# Greinke_Boost_Converter_Motor_Schematic.net
KiCad netlist of a schematic drawn in Altium Designer
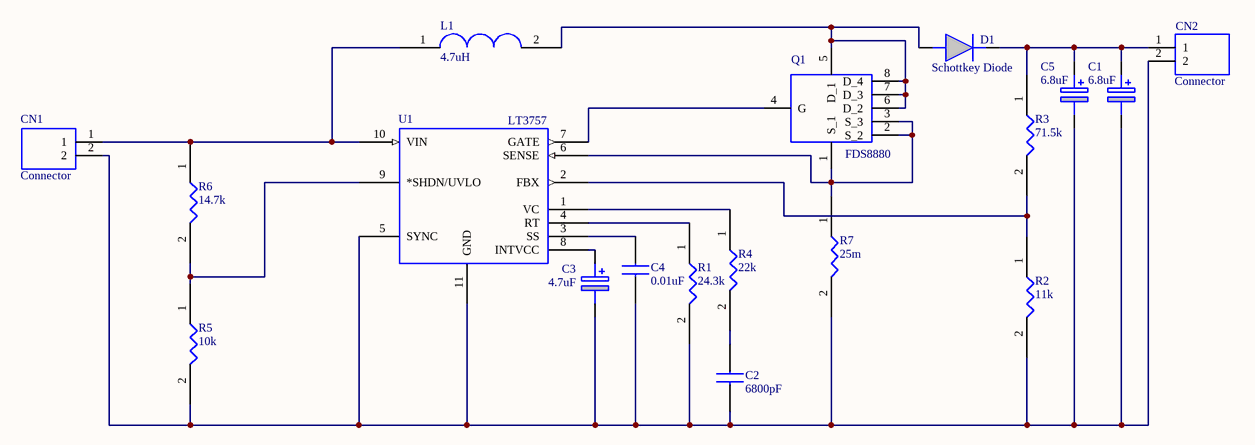
[diagram p0: Greinke_Boost_Converter_Motor(Schematic).SchDoc]

(export (version "E")
  (design (tool "Eeschema 10.0.6"))
  (components
    (comp (ref "C1")
      (value "6.8uF")
      (footprint "6.8u Capacitor")
      (libsource (lib "Schlib1") (part "6.8u Capacitor"))
    )
    (comp (ref "C2")
      (value "6800pF")
      (footprint "6800p Capacitor")
      (libsource (lib "Schlib1") (part "6800p Capacitor"))
    )
    (comp (ref "C3")
      (value "4.7uF")
      (footprint "4.7u Capacitor")
      (libsource (lib "Schlib1") (part "4.7u Capacitor"))
    )
    (comp (ref "C4")
      (value "0.01uF")
      (footprint "0.01u Capacitor")
      (libsource (lib "Schlib1") (part "0.01u Capacitor_1"))
    )
    (comp (ref "C5")
      (value "6.8uF")
      (footprint "6.8u Capacitor")
      (libsource (lib "Schlib1") (part "6.8u Capacitor"))
    )
    (comp (ref "CN1")
      (value "Connector")
      (footprint "2 Terminal Blocks")
      (libsource (lib "") (part "2 Terminal Blocks_1"))
    )
    (comp (ref "CN2")
      (value "Connector")
      (footprint "2 Terminal Blocks")
      (libsource (lib "Schlib1") (part "2 Terminal Blocks"))
    )
    (comp (ref "D1")
      (value "Schottkey Diode")
      (footprint "MBRS340")
      (libsource (lib "Schlib1") (part "MBRS340"))
    )
    (comp (ref "L1") (value "4.7uH") (footprint "744774047") (libsource (lib "Schlib1") (part "744774047")))
    (comp (ref "Q1") (value "FDS8880") (footprint "FDS8880") (libsource (lib "Schlib1") (part "FDS8880")))
    (comp (ref "R1")
      (value "24.3k")
      (footprint "24.3k Resistor")
      (libsource (lib "Schlib1") (part "24.3k Resistor"))
    )
    (comp (ref "R2")
      (value "11k")
      (footprint "11k Resistor")
      (libsource (lib "Schlib1") (part "11k Resistor"))
    )
    (comp (ref "R3")
      (value "71.5k")
      (footprint "71.5k Resistor")
      (libsource (lib "Schlib1") (part "71.5k Resistor"))
    )
    (comp (ref "R4")
      (value "22k")
      (footprint "22k Resistor")
      (libsource (lib "Schlib1") (part "22k Resistor"))
    )
    (comp (ref "R5")
      (value "10k")
      (footprint "10k Resistor")
      (libsource (lib "Schlib1") (part "10k Resistor"))
    )
    (comp (ref "R6")
      (value "14.7k")
      (footprint "14.7k Resistor")
      (libsource (lib "Schlib1") (part "14.7k Resistor"))
    )
    (comp (ref "R7")
      (value "25m")
      (footprint "25m Resistor")
      (libsource (lib "Schlib1") (part "25m Resistor"))
    )
    (comp (ref "U1") (value "LT3757") (footprint "LT3757") (libsource (lib "Schlib1") (part "LT3757")))
  )
  (nets
    (net (code "1") (name "Net-(C1-+)") (class "Default")
      (node (ref "C1") (pin "1") (pinfunction "+_1") (pintype "passive"))
      (node (ref "C5") (pin "1") (pinfunction "+_1") (pintype "passive"))
      (node (ref "CN2") (pin "1") (pinfunction "1_1") (pintype "passive"))
      (node (ref "D1") (pin "1") (pinfunction "K_1") (pintype "passive"))
      (node (ref "R3") (pin "1") (pintype "passive"))
    )
    (net (code "2") (name "Net-(C1--)") (class "Default")
      (node (ref "C1") (pin "2") (pinfunction "-_2") (pintype "passive"))
      (node (ref "C2") (pin "2") (pinfunction "2_2") (pintype "passive"))
      (node (ref "C3") (pin "2") (pinfunction "-_2") (pintype "passive"))
      (node (ref "C4") (pin "1") (pinfunction "1_1") (pintype "passive"))
      (node (ref "C5") (pin "2") (pinfunction "-_2") (pintype "passive"))
      (node (ref "CN1") (pin "2") (pinfunction "2_2") (pintype "passive"))
      (node (ref "CN2") (pin "2") (pinfunction "2_2") (pintype "passive"))
      (node (ref "R1") (pin "2") (pintype "passive"))
      (node (ref "R2") (pin "2") (pintype "passive"))
      (node (ref "R5") (pin "2") (pintype "passive"))
      (node (ref "R7") (pin "2") (pintype "passive"))
      (node (ref "U1") (pin "11") (pinfunction "GND_11") (pintype "passive"))
      (node (ref "U1") (pin "5") (pinfunction "SYNC_5") (pintype "passive"))
    )
    (net (code "3") (name "Net-(C2-Pad1)") (class "Default")
      (node (ref "C2") (pin "1") (pinfunction "1_1") (pintype "passive"))
      (node (ref "R4") (pin "2") (pintype "passive"))
    )
    (net (code "4") (name "Net-(C3-+)") (class "Default")
      (node (ref "C3") (pin "1") (pinfunction "+_1") (pintype "passive"))
      (node (ref "U1") (pin "8") (pinfunction "INTVCC_8") (pintype "passive"))
    )
    (net (code "5") (name "Net-(D1-A)") (class "Default")
      (node (ref "D1") (pin "2") (pinfunction "A_2") (pintype "passive"))
      (node (ref "L1") (pin "2") (pintype "passive"))
      (node (ref "Q1") (pin "5") (pinfunction "D_1_5") (pintype "passive"))
      (node (ref "Q1") (pin "6") (pinfunction "D_2_6") (pintype "passive"))
      (node (ref "Q1") (pin "7") (pinfunction "D_3_7") (pintype "passive"))
      (node (ref "Q1") (pin "8") (pinfunction "D_4_8") (pintype "passive"))
    )
    (net (code "6") (name "Net-(Q1-G)") (class "Default")
      (node (ref "Q1") (pin "4") (pinfunction "G_4") (pintype "passive"))
      (node (ref "U1") (pin "7") (pinfunction "GATE_7") (pintype "output"))
    )
    (net (code "7") (name "Net-(Q1-S_1)") (class "Default")
      (node (ref "Q1") (pin "1") (pinfunction "S_1_1") (pintype "passive"))
      (node (ref "Q1") (pin "2") (pinfunction "S_2_2") (pintype "passive"))
      (node (ref "Q1") (pin "3") (pinfunction "S_3_3") (pintype "passive"))
      (node (ref "R7") (pin "1") (pintype "passive"))
      (node (ref "U1") (pin "6") (pinfunction "SENSE_6") (pintype "input"))
    )
    (net (code "8") (name "Net-(U1-*SHDN{slash}UVLO)") (class "Default")
      (node (ref "R5") (pin "1") (pintype "passive"))
      (node (ref "R6") (pin "2") (pintype "passive"))
      (node (ref "U1") (pin "9") (pinfunction "*SHDN/UVLO_9") (pintype "passive"))
    )
    (net (code "9") (name "Net-(U1-FBX)") (class "Default")
      (node (ref "R2") (pin "1") (pintype "passive"))
      (node (ref "R3") (pin "2") (pintype "passive"))
      (node (ref "U1") (pin "2") (pinfunction "FBX_2") (pintype "output"))
    )
    (net (code "10") (name "Net-(U1-RT)") (class "Default")
      (node (ref "R1") (pin "1") (pintype "passive"))
      (node (ref "U1") (pin "4") (pinfunction "RT_4") (pintype "passive"))
    )
    (net (code "11") (name "Net-(U1-SS)") (class "Default")
      (node (ref "C4") (pin "2") (pinfunction "2_2") (pintype "passive"))
      (node (ref "U1") (pin "3") (pinfunction "SS_3") (pintype "passive"))
    )
    (net (code "12") (name "Net-(U1-VC)") (class "Default")
      (node (ref "R4") (pin "1") (pintype "passive"))
      (node (ref "U1") (pin "1") (pinfunction "VC_1") (pintype "passive"))
    )
    (net (code "13") (name "Net-(U1-VIN)") (class "Default")
      (node (ref "CN1") (pin "1") (pinfunction "1_1") (pintype "passive"))
      (node (ref "L1") (pin "1") (pintype "passive"))
      (node (ref "R6") (pin "1") (pintype "passive"))
      (node (ref "U1") (pin "10") (pinfunction "VIN_10") (pintype "input"))
    )
  )
)
